# 3_waffling60-MXHS-ISO_mcu.net
KiCad netlist of a schematic drawn in Altium Designer
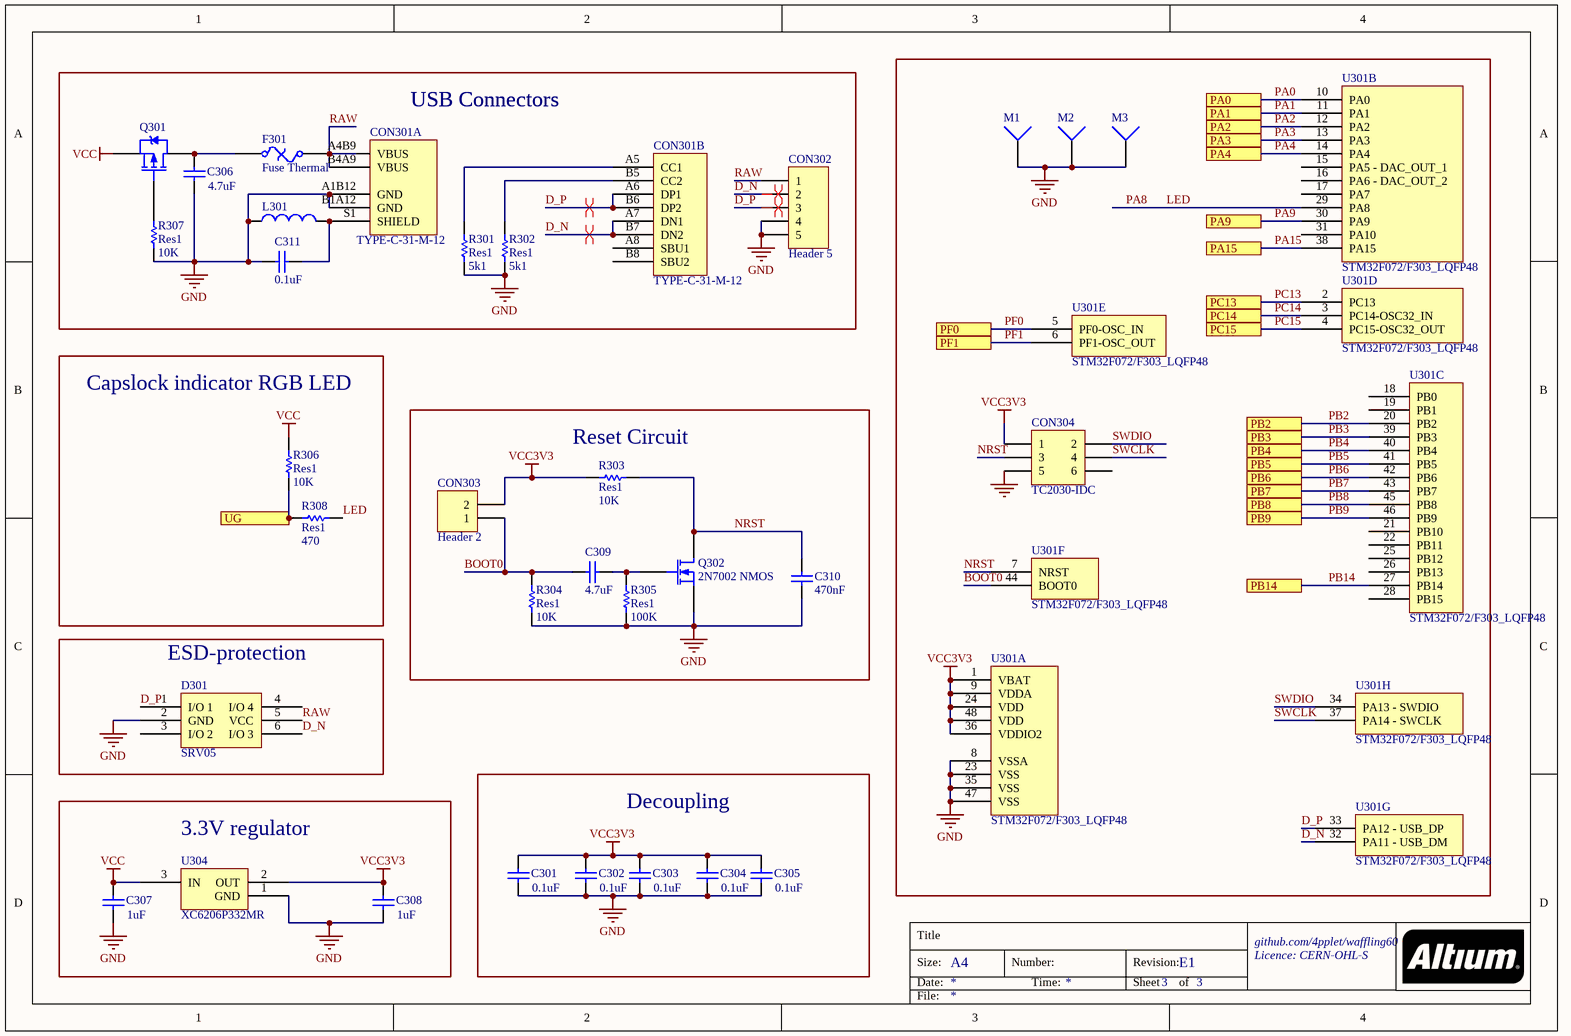
[diagram p0: 3_waffling60-MXHS-ISO_mcu.SchDoc]

(export (version "E")
  (design (tool "Eeschema 10.0.6"))
  (components
    (comp (ref "C301")
      (value "0.1uF")
      (footprint "C0603[1608]")
      (description "Capacitor")
      (fields (field (name "LCSC PART #") "C14663") (field (name "MRF.PART") "CC0603KRX7R9BB104"))
      (libsource (lib "Miscellaneous Devices") (part "Cap"))
    )
    (comp (ref "C302")
      (value "0.1uF")
      (footprint "C0603[1608]")
      (description "Capacitor")
      (fields (field (name "LCSC PART #") "C14663") (field (name "MRF.PART") "CC0603KRX7R9BB104"))
      (libsource (lib "Miscellaneous Devices") (part "Cap"))
    )
    (comp (ref "C303")
      (value "0.1uF")
      (footprint "C0603[1608]")
      (description "Capacitor")
      (fields (field (name "LCSC PART #") "C14663") (field (name "MRF.PART") "CC0603KRX7R9BB104"))
      (libsource (lib "Miscellaneous Devices") (part "Cap"))
    )
    (comp (ref "C304")
      (value "0.1uF")
      (footprint "C0603[1608]")
      (description "Capacitor")
      (fields (field (name "LCSC PART #") "C14663") (field (name "MRF.PART") "CC0603KRX7R9BB104"))
      (libsource (lib "Miscellaneous Devices") (part "Cap"))
    )
    (comp (ref "C305")
      (value "0.1uF")
      (footprint "C0603[1608]")
      (description "Capacitor")
      (fields (field (name "LCSC PART #") "C14663") (field (name "MRF.PART") "CC0603KRX7R9BB104"))
      (libsource (lib "Miscellaneous Devices") (part "Cap"))
    )
    (comp (ref "C306")
      (value "4.7uF")
      (footprint "C0603[1608]")
      (description "Capacitor")
      (fields (field (name "LCSC PART #") "C19666") (field (name "MRF.PART") "CL10A475KO8NNNC"))
      (libsource (lib "Miscellaneous Devices") (part "Cap"))
    )
    (comp (ref "C307")
      (value "1uF")
      (footprint "C0603[1608]")
      (description "Capacitor")
      (fields (field (name "LCSC PART #") "C15849") (field (name "MRF.PART") "CL10A105KB8NNNC"))
      (libsource (lib "Miscellaneous Devices") (part "Cap"))
    )
    (comp (ref "C308")
      (value "1uF")
      (footprint "C0603[1608]")
      (description "Capacitor")
      (fields (field (name "LCSC PART #") "C15849") (field (name "MRF.PART") "CL10A105KB8NNNC"))
      (libsource (lib "Miscellaneous Devices") (part "Cap"))
    )
    (comp (ref "C309")
      (value "4.7uF")
      (footprint "C0603[1608]")
      (description "Capacitor")
      (fields (field (name "LCSC PART #") "C19666") (field (name "MRF.PART") "CL10A475KO8NNNC"))
      (libsource (lib "Miscellaneous Devices") (part "Cap"))
    )
    (comp (ref "C310")
      (value "470nF")
      (footprint "C0603[1608]")
      (description "Capacitor")
      (fields (field (name "LCSC PART #") "C1623") (field (name "MRF.PART") "CL10B474KA8NNNC"))
      (libsource (lib "Miscellaneous Devices") (part "Cap"))
    )
    (comp (ref "C311")
      (value "0.1uF")
      (footprint "C0603[1608]")
      (description "Capacitor")
      (fields (field (name "LCSC PART #") "C14663") (field (name "MRF.PART") "CC0603KRX7R9BB104"))
      (libsource (lib "Miscellaneous Devices") (part "Cap"))
    )
    (comp (ref "CON301")
      (value "TYPE-C-31-M-12")
      (footprint "TYPE-C-31-M-12")
      (fields (field (name "LCSC PART #") "C165948"))
      (libsource (lib "Schlib1") (part "TYPE-C-31-M-12"))
    )
    (comp (ref "CON302")
      (value "Header 5")
      (footprint "UDB_combo_JST_MOLEX")
      (description "JST for USB daughter board")
      (fields (field (name "LCSC PART #") "C145956"))
      (libsource (lib "Miscellaneous Connectors") (part "Header 5"))
    )
    (comp (ref "CON303")
      (value "Header 2")
      (footprint "HDR1X2")
      (description "Header, 2-Pin")
      (libsource (lib "Miscellaneous Connectors") (part "Header 2"))
    )
    (comp (ref "CON304")
      (value "TC2030-IDC")
      (footprint "TC2030-IDC-NL")
      (description "Header, 3-Pin, Dual row")
      (libsource (lib "Miscellaneous Connectors") (part "Header 3X2"))
    )
    (comp (ref "D301")
      (value "SRV05")
      (footprint "SOT-23-6")
      (fields (field (name "LCSC PART #") "C85364") (field (name "MRF.PART") "SRV05-4-P-T7"))
      (libsource (lib "Keebs") (part "SRV05"))
    )
    (comp (ref "F301")
      (value "Fuse Thermal")
      (footprint "C1206[3216]")
      (description "Thermal Fuse")
      (fields (field (name "LCSC PART #") "C135338") (field (name "MRF.PART") "ASMD1206-050"))
      (libsource (lib "Miscellaneous Devices") (part "Fuse Thermal"))
    )
    (comp (ref "L301")
      (value "Inductor")
      (footprint "L0805")
      (fields (field (name "LCSC PART #") "C1015") (field (name "MRF.PART") "GZ2012D101TF"))
      (libsource (lib "Simulation Generic Components") (part "Inductor"))
    )
    (comp (ref "M1")
      (value "Socket")
      (footprint "mounting_hole")
      (libsource (lib "Miscellaneous Connectors") (part "Socket"))
    )
    (comp (ref "M2")
      (value "Socket")
      (footprint "mounting_hole")
      (libsource (lib "Miscellaneous Connectors") (part "Socket"))
    )
    (comp (ref "M3")
      (value "Socket")
      (footprint "mounting_hole")
      (libsource (lib "Miscellaneous Connectors") (part "Socket"))
    )
    (comp (ref "Q301")
      (value "PMOS-2")
      (footprint "SOT-23-3")
      (description "P-Channel Power MOSFET")
      (fields (field (name "LCSC PART #") "C10487") (field (name "MRF.PART") "SI2301CDS-T1-GE3"))
      (libsource (lib "Miscellaneous Devices") (part "PMOS-2"))
    )
    (comp (ref "Q302")
      (value "2N7002 NMOS")
      (footprint "SOT-23-3")
      (description "N-Channel MOSFET")
      (fields (field (name "LCSC PART #") "C8545") (field (name "MRF.PART") "2N7002"))
      (libsource (lib "Miscellaneous Devices") (part "MOSFET-N"))
    )
    (comp (ref "R301")
      (value "Res1")
      (footprint "R0603[1608]")
      (description "Resistor")
      (fields
        (field (name "ALTIUM_VALUE") "5k1")
        (field (name "LCSC PART #") "C23186")
        (field (name "MRF.PART") "0603WAF5101T5E")
      )
      (libsource (lib "Miscellaneous Devices") (part "Res1"))
    )
    (comp (ref "R302")
      (value "Res1")
      (footprint "R0603[1608]")
      (description "Resistor")
      (fields
        (field (name "ALTIUM_VALUE") "5k1")
        (field (name "LCSC PART #") "C23186")
        (field (name "MRF.PART") "0603WAF5101T5E")
      )
      (libsource (lib "Miscellaneous Devices") (part "Res1"))
    )
    (comp (ref "R303")
      (value "Res1")
      (footprint "R0603[1608]")
      (description "Resistor")
      (fields
        (field (name "ALTIUM_VALUE") "10K")
        (field (name "LCSC PART #") "C25804")
        (field (name "MRF.PART") "0603WAF1002T5E")
      )
      (libsource (lib "Miscellaneous Devices") (part "Res1"))
    )
    (comp (ref "R304")
      (value "Res1")
      (footprint "R0603[1608]")
      (description "Resistor")
      (fields
        (field (name "ALTIUM_VALUE") "10K")
        (field (name "LCSC PART #") "C25804")
        (field (name "MRF.PART") "0603WAF1002T5E")
      )
      (libsource (lib "Miscellaneous Devices") (part "Res1"))
    )
    (comp (ref "R305")
      (value "Res1")
      (footprint "R0603[1608]")
      (description "Resistor")
      (fields
        (field (name "ALTIUM_VALUE") "100K")
        (field (name "LCSC PART #") "C25803")
        (field (name "MRF.PART") "0603WAF1003T5E")
      )
      (libsource (lib "Miscellaneous Devices") (part "Res1"))
    )
    (comp (ref "R306")
      (value "Res1")
      (footprint "R0603[1608]")
      (description "Resistor")
      (fields
        (field (name "ALTIUM_VALUE") "10K")
        (field (name "LCSC PART #") "C25804")
        (field (name "MRF.PART") "0603WAF1002T5E")
      )
      (libsource (lib "Miscellaneous Devices") (part "Res1"))
    )
    (comp (ref "R307")
      (value "Res1")
      (footprint "R0603[1608]")
      (description "Resistor")
      (fields
        (field (name "ALTIUM_VALUE") "10K")
        (field (name "LCSC PART #") "C25804")
        (field (name "MRF.PART") "0603WAF1002T5E")
      )
      (libsource (lib "Miscellaneous Devices") (part "Res1"))
    )
    (comp (ref "R308")
      (value "Res1")
      (footprint "R0603[1608]")
      (description "Resistor")
      (fields
        (field (name "ALTIUM_VALUE") "470")
        (field (name "LCSC PART #") "C23179")
        (field (name "MRF.PART") "0603WAF4700T5E")
      )
      (libsource (lib "Miscellaneous Devices") (part "Res1"))
    )
    (comp (ref "U301")
      (value "STM32F072/F303_LQFP48")
      (footprint "STM32 - COMBO 7X7MM")
      (fields (field (name "LCSC PART #") "C915660") (field (name "MRF.PART") "APM32F072CBT6"))
      (libsource (lib "Keebs") (part "STM32F072/F303_LQFP48"))
    )
    (comp (ref "U304")
      (value "XC6206P332MR")
      (footprint "SOT-23-3")
      (fields (field (name "LCSC PART #") "C5446"))
      (libsource (lib "Keebs") (part "SOT23 LDO"))
    )
  )
  (nets
    (net (code "1") (name "/BOOT0") (class "Default")
      (node (ref "C309") (pin "1") (pinfunction "1_1") (pintype "passive"))
      (node (ref "CON303") (pin "1") (pinfunction "1_1") (pintype "passive"))
      (node (ref "R304") (pin "1") (pinfunction "1_1") (pintype "passive"))
      (node (ref "U301") (pin "44") (pinfunction "BOOT0_44") (pintype "passive"))
    )
    (net (code "2") (name "/D_N") (class "Default")
      (node (ref "CON301") (pin "A7") (pinfunction "DN1_A7") (pintype "passive"))
      (node (ref "CON301") (pin "B7") (pinfunction "DN2_B7") (pintype "passive"))
      (node (ref "CON302") (pin "2") (pinfunction "2_2") (pintype "passive"))
      (node (ref "D301") (pin "6") (pinfunction "I/O_3_6") (pintype "passive"))
      (node (ref "U301") (pin "32") (pinfunction "PA11_-_USB_DM_32") (pintype "passive"))
    )
    (net (code "3") (name "/D_P") (class "Default")
      (node (ref "CON301") (pin "A6") (pinfunction "DP1_A6") (pintype "passive"))
      (node (ref "CON301") (pin "B6") (pinfunction "DP2_B6") (pintype "passive"))
      (node (ref "CON302") (pin "3") (pinfunction "3_3") (pintype "passive"))
      (node (ref "D301") (pin "1") (pinfunction "I/O_1_1") (pintype "passive"))
      (node (ref "U301") (pin "33") (pinfunction "PA12_-_USB_DP_33") (pintype "passive"))
    )
    (net (code "4") (name "/LED") (class "Default")
      (node (ref "R308") (pin "2") (pinfunction "2_2") (pintype "passive"))
      (node (ref "U301") (pin "29") (pinfunction "PA8_29") (pintype "passive"))
    )
    (net (code "5") (name "/NRST") (class "Default")
      (node (ref "C310") (pin "1") (pinfunction "1_1") (pintype "passive"))
      (node (ref "CON304") (pin "3") (pinfunction "3_3") (pintype "passive"))
      (node (ref "Q302") (pin "3") (pinfunction "D_3") (pintype "passive"))
      (node (ref "R303") (pin "2") (pinfunction "2_2") (pintype "passive"))
      (node (ref "U301") (pin "7") (pinfunction "NRST_7") (pintype "passive"))
    )
    (net (code "6") (name "/PA0") (class "Default")
      (node (ref "U301") (pin "10") (pinfunction "PA0_10") (pintype "passive"))
    )
    (net (code "7") (name "/PA1") (class "Default")
      (node (ref "U301") (pin "11") (pinfunction "PA1_11") (pintype "passive"))
    )
    (net (code "8") (name "/PA2") (class "Default")
      (node (ref "U301") (pin "12") (pinfunction "PA2_12") (pintype "passive"))
    )
    (net (code "9") (name "/PA3") (class "Default")
      (node (ref "U301") (pin "13") (pinfunction "PA3_13") (pintype "passive"))
    )
    (net (code "10") (name "/PA4") (class "Default")
      (node (ref "U301") (pin "14") (pinfunction "PA4_14") (pintype "passive"))
    )
    (net (code "11") (name "/PA9") (class "Default")
      (node (ref "U301") (pin "30") (pinfunction "PA9_30") (pintype "passive"))
    )
    (net (code "12") (name "/PA15") (class "Default")
      (node (ref "U301") (pin "38") (pinfunction "PA15_38") (pintype "passive"))
    )
    (net (code "13") (name "/PB2") (class "Default")
      (node (ref "U301") (pin "20") (pinfunction "PB2_20") (pintype "passive"))
    )
    (net (code "14") (name "/PB3") (class "Default")
      (node (ref "U301") (pin "39") (pinfunction "PB3_39") (pintype "passive"))
    )
    (net (code "15") (name "/PB4") (class "Default")
      (node (ref "U301") (pin "40") (pinfunction "PB4_40") (pintype "passive"))
    )
    (net (code "16") (name "/PB5") (class "Default")
      (node (ref "U301") (pin "41") (pinfunction "PB5_41") (pintype "passive"))
    )
    (net (code "17") (name "/PB6") (class "Default")
      (node (ref "U301") (pin "42") (pinfunction "PB6_42") (pintype "passive"))
    )
    (net (code "18") (name "/PB7") (class "Default")
      (node (ref "U301") (pin "43") (pinfunction "PB7_43") (pintype "passive"))
    )
    (net (code "19") (name "/PB8") (class "Default")
      (node (ref "U301") (pin "45") (pinfunction "PB8_45") (pintype "passive"))
    )
    (net (code "20") (name "/PB9") (class "Default")
      (node (ref "U301") (pin "46") (pinfunction "PB9_46") (pintype "passive"))
    )
    (net (code "21") (name "/PB14") (class "Default")
      (node (ref "U301") (pin "27") (pinfunction "PB14_27") (pintype "passive"))
    )
    (net (code "22") (name "/PC13") (class "Default")
      (node (ref "U301") (pin "2") (pinfunction "PC13_2") (pintype "passive"))
    )
    (net (code "23") (name "/PC14") (class "Default")
      (node (ref "U301") (pin "3") (pinfunction "PC14-OSC32_IN_3") (pintype "passive"))
    )
    (net (code "24") (name "/PC15") (class "Default")
      (node (ref "U301") (pin "4") (pinfunction "PC15-OSC32_OUT_4") (pintype "passive"))
    )
    (net (code "25") (name "/PF0") (class "Default")
      (node (ref "U301") (pin "5") (pinfunction "PF0-OSC_IN_5") (pintype "passive"))
    )
    (net (code "26") (name "/PF1") (class "Default")
      (node (ref "U301") (pin "6") (pinfunction "PF1-OSC_OUT_6") (pintype "passive"))
    )
    (net (code "27") (name "/RAW") (class "Default")
      (node (ref "CON301") (pin "A4B9") (pinfunction "VBUS_A4B9") (pintype "passive"))
      (node (ref "CON301") (pin "B4A9") (pinfunction "VBUS_B4A9") (pintype "passive"))
      (node (ref "CON302") (pin "1") (pinfunction "1_1") (pintype "passive"))
      (node (ref "D301") (pin "5") (pinfunction "VCC_5") (pintype "passive"))
      (node (ref "F301") (pin "2") (pinfunction "2_2") (pintype "passive"))
    )
    (net (code "28") (name "/SWCLK") (class "Default")
      (node (ref "CON304") (pin "4") (pinfunction "4_4") (pintype "passive"))
      (node (ref "U301") (pin "37") (pinfunction "PA14_-_SWCLK_37") (pintype "passive"))
    )
    (net (code "29") (name "/SWDIO") (class "Default")
      (node (ref "CON304") (pin "2") (pinfunction "2_2") (pintype "passive"))
      (node (ref "U301") (pin "34") (pinfunction "PA13_-_SWDIO_34") (pintype "passive"))
    )
    (net (code "30") (name "/UG") (class "Default")
      (node (ref "R306") (pin "2") (pinfunction "2_2") (pintype "passive"))
      (node (ref "R308") (pin "1") (pinfunction "1_1") (pintype "passive"))
    )
    (net (code "31") (name "GND") (class "Default")
      (node (ref "C301") (pin "1") (pinfunction "1_1") (pintype "passive"))
      (node (ref "C302") (pin "1") (pinfunction "1_1") (pintype "passive"))
      (node (ref "C303") (pin "1") (pinfunction "1_1") (pintype "passive"))
      (node (ref "C304") (pin "1") (pinfunction "1_1") (pintype "passive"))
      (node (ref "C305") (pin "1") (pinfunction "1_1") (pintype "passive"))
      (node (ref "C306") (pin "1") (pinfunction "1_1") (pintype "passive"))
      (node (ref "C307") (pin "1") (pinfunction "1_1") (pintype "passive"))
      (node (ref "C308") (pin "1") (pinfunction "1_1") (pintype "passive"))
      (node (ref "C310") (pin "2") (pinfunction "2_2") (pintype "passive"))
      (node (ref "C311") (pin "1") (pinfunction "1_1") (pintype "passive"))
      (node (ref "CON301") (pin "A1B12") (pinfunction "GND_A1B12") (pintype "passive"))
      (node (ref "CON301") (pin "B1A12") (pinfunction "GND_B1A12") (pintype "passive"))
      (node (ref "CON302") (pin "4") (pinfunction "4_4") (pintype "passive"))
      (node (ref "CON302") (pin "5") (pinfunction "5_5") (pintype "passive"))
      (node (ref "CON304") (pin "5") (pinfunction "5_5") (pintype "passive"))
      (node (ref "D301") (pin "2") (pinfunction "GND_2") (pintype "passive"))
      (node (ref "L301") (pin "1") (pinfunction "1_1") (pintype "passive"))
      (node (ref "M1") (pin "1") (pinfunction "1_1") (pintype "passive"))
      (node (ref "M2") (pin "1") (pinfunction "1_1") (pintype "passive"))
      (node (ref "M3") (pin "1") (pinfunction "1_1") (pintype "passive"))
      (node (ref "Q302") (pin "2") (pinfunction "S_2") (pintype "passive"))
      (node (ref "R301") (pin "2") (pinfunction "2_2") (pintype "passive"))
      (node (ref "R302") (pin "2") (pinfunction "2_2") (pintype "passive"))
      (node (ref "R304") (pin "2") (pinfunction "2_2") (pintype "passive"))
      (node (ref "R305") (pin "2") (pinfunction "2_2") (pintype "passive"))
      (node (ref "R307") (pin "2") (pinfunction "2_2") (pintype "passive"))
      (node (ref "U301") (pin "23") (pinfunction "VSS_23") (pintype "passive"))
      (node (ref "U301") (pin "35") (pinfunction "VSS_35") (pintype "passive"))
      (node (ref "U301") (pin "47") (pinfunction "VSS_47") (pintype "passive"))
      (node (ref "U301") (pin "8") (pinfunction "VSSA_8") (pintype "passive"))
      (node (ref "U304") (pin "1") (pinfunction "GND_1") (pintype "passive"))
    )
    (net (code "32") (name "Net-(CON301A-SHIELD)") (class "Default")
      (node (ref "C311") (pin "2") (pinfunction "2_2") (pintype "passive"))
      (node (ref "CON301") (pin "S1") (pinfunction "SHIELD_S1") (pintype "passive"))
      (node (ref "L301") (pin "2") (pinfunction "2_2") (pintype "passive"))
    )
    (net (code "33") (name "Net-(CON301B-CC1)") (class "Default")
      (node (ref "CON301") (pin "A5") (pinfunction "CC1_A5") (pintype "passive"))
      (node (ref "R301") (pin "1") (pinfunction "1_1") (pintype "passive"))
    )
    (net (code "34") (name "Net-(CON301B-CC2)") (class "Default")
      (node (ref "CON301") (pin "B5") (pinfunction "CC2_B5") (pintype "passive"))
      (node (ref "R302") (pin "1") (pinfunction "1_1") (pintype "passive"))
    )
    (net (code "35") (name "Net-(Q301-D)") (class "Default")
      (node (ref "C306") (pin "2") (pinfunction "2_2") (pintype "passive"))
      (node (ref "F301") (pin "1") (pinfunction "1_1") (pintype "passive"))
      (node (ref "Q301") (pin "3") (pinfunction "D_3") (pintype "passive"))
    )
    (net (code "36") (name "Net-(Q301-G)") (class "Default")
      (node (ref "Q301") (pin "1") (pinfunction "G_1") (pintype "passive"))
      (node (ref "R307") (pin "1") (pinfunction "1_1") (pintype "passive"))
    )
    (net (code "37") (name "Net-(Q302-G)") (class "Default")
      (node (ref "C309") (pin "2") (pinfunction "2_2") (pintype "passive"))
      (node (ref "Q302") (pin "1") (pinfunction "G_1") (pintype "passive"))
      (node (ref "R305") (pin "1") (pinfunction "1_1") (pintype "passive"))
    )
    (net (code "38") (name "VCC") (class "Default")
      (node (ref "C307") (pin "2") (pinfunction "2_2") (pintype "passive"))
      (node (ref "Q301") (pin "2") (pinfunction "S_2") (pintype "passive"))
      (node (ref "R306") (pin "1") (pinfunction "1_1") (pintype "passive"))
      (node (ref "U304") (pin "3") (pinfunction "IN_3") (pintype "passive"))
    )
    (net (code "39") (name "VCC3V3") (class "Default")
      (node (ref "C301") (pin "2") (pinfunction "2_2") (pintype "passive"))
      (node (ref "C302") (pin "2") (pinfunction "2_2") (pintype "passive"))
      (node (ref "C303") (pin "2") (pinfunction "2_2") (pintype "passive"))
      (node (ref "C304") (pin "2") (pinfunction "2_2") (pintype "passive"))
      (node (ref "C305") (pin "2") (pinfunction "2_2") (pintype "passive"))
      (node (ref "C308") (pin "2") (pinfunction "2_2") (pintype "passive"))
      (node (ref "CON303") (pin "2") (pinfunction "2_2") (pintype "passive"))
      (node (ref "CON304") (pin "1") (pinfunction "1_1") (pintype "passive"))
      (node (ref "R303") (pin "1") (pinfunction "1_1") (pintype "passive"))
      (node (ref "U301") (pin "1") (pinfunction "VBAT_1") (pintype "passive"))
      (node (ref "U301") (pin "24") (pinfunction "VDD_24") (pintype "passive"))
      (node (ref "U301") (pin "36") (pinfunction "VDDIO2_36") (pintype "passive"))
      (node (ref "U301") (pin "48") (pinfunction "VDD_48") (pintype "passive"))
      (node (ref "U301") (pin "9") (pinfunction "VDDA_9") (pintype "passive"))
      (node (ref "U304") (pin "2") (pinfunction "OUT_2") (pintype "passive"))
    )
    (net (code "40") (name "unconnected-(CON301B-SBU1-PadA8)") (class "Default")
      (node (ref "CON301") (pin "A8") (pinfunction "SBU1_A8") (pintype "passive"))
    )
    (net (code "41") (name "unconnected-(CON301B-SBU2-PadB8)") (class "Default")
      (node (ref "CON301") (pin "B8") (pinfunction "SBU2_B8") (pintype "passive"))
    )
    (net (code "42") (name "unconnected-(CON304-Pad6)") (class "Default")
      (node (ref "CON304") (pin "6") (pinfunction "6_6") (pintype "passive"))
    )
    (net (code "43") (name "unconnected-(D301-I{slash}O_2-Pad3)") (class "Default")
      (node (ref "D301") (pin "3") (pinfunction "I/O_2_3") (pintype "passive"))
    )
    (net (code "44") (name "unconnected-(D301-I{slash}O_4-Pad4)") (class "Default")
      (node (ref "D301") (pin "4") (pinfunction "I/O_4_4") (pintype "passive"))
    )
    (net (code "45") (name "unconnected-(U301B-PA5_-_DAC_OUT_1-Pad15)") (class "Default")
      (node (ref "U301") (pin "15") (pinfunction "PA5_-_DAC_OUT_1_15") (pintype "passive"))
    )
    (net (code "46") (name "unconnected-(U301B-PA6_-_DAC_OUT_2-Pad16)") (class "Default")
      (node (ref "U301") (pin "16") (pinfunction "PA6_-_DAC_OUT_2_16") (pintype "passive"))
    )
    (net (code "47") (name "unconnected-(U301B-PA7-Pad17)") (class "Default")
      (node (ref "U301") (pin "17") (pinfunction "PA7_17") (pintype "passive"))
    )
    (net (code "48") (name "unconnected-(U301B-PA10-Pad31)") (class "Default")
      (node (ref "U301") (pin "31") (pinfunction "PA10_31") (pintype "passive"))
    )
    (net (code "49") (name "unconnected-(U301C-PB0-Pad18)") (class "Default")
      (node (ref "U301") (pin "18") (pinfunction "PB0_18") (pintype "passive"))
    )
    (net (code "50") (name "unconnected-(U301C-PB1-Pad19)") (class "Default")
      (node (ref "U301") (pin "19") (pinfunction "PB1_19") (pintype "passive"))
    )
    (net (code "51") (name "unconnected-(U301C-PB10-Pad21)") (class "Default")
      (node (ref "U301") (pin "21") (pinfunction "PB10_21") (pintype "passive"))
    )
    (net (code "52") (name "unconnected-(U301C-PB11-Pad22)") (class "Default")
      (node (ref "U301") (pin "22") (pinfunction "PB11_22") (pintype "passive"))
    )
    (net (code "53") (name "unconnected-(U301C-PB12-Pad25)") (class "Default")
      (node (ref "U301") (pin "25") (pinfunction "PB12_25") (pintype "passive"))
    )
    (net (code "54") (name "unconnected-(U301C-PB13-Pad26)") (class "Default")
      (node (ref "U301") (pin "26") (pinfunction "PB13_26") (pintype "passive"))
    )
    (net (code "55") (name "unconnected-(U301C-PB15-Pad28)") (class "Default")
      (node (ref "U301") (pin "28") (pinfunction "PB15_28") (pintype "passive"))
    )
  )
)
